# Top_Level.net
KiCad netlist of a schematic drawn in Altium Designer
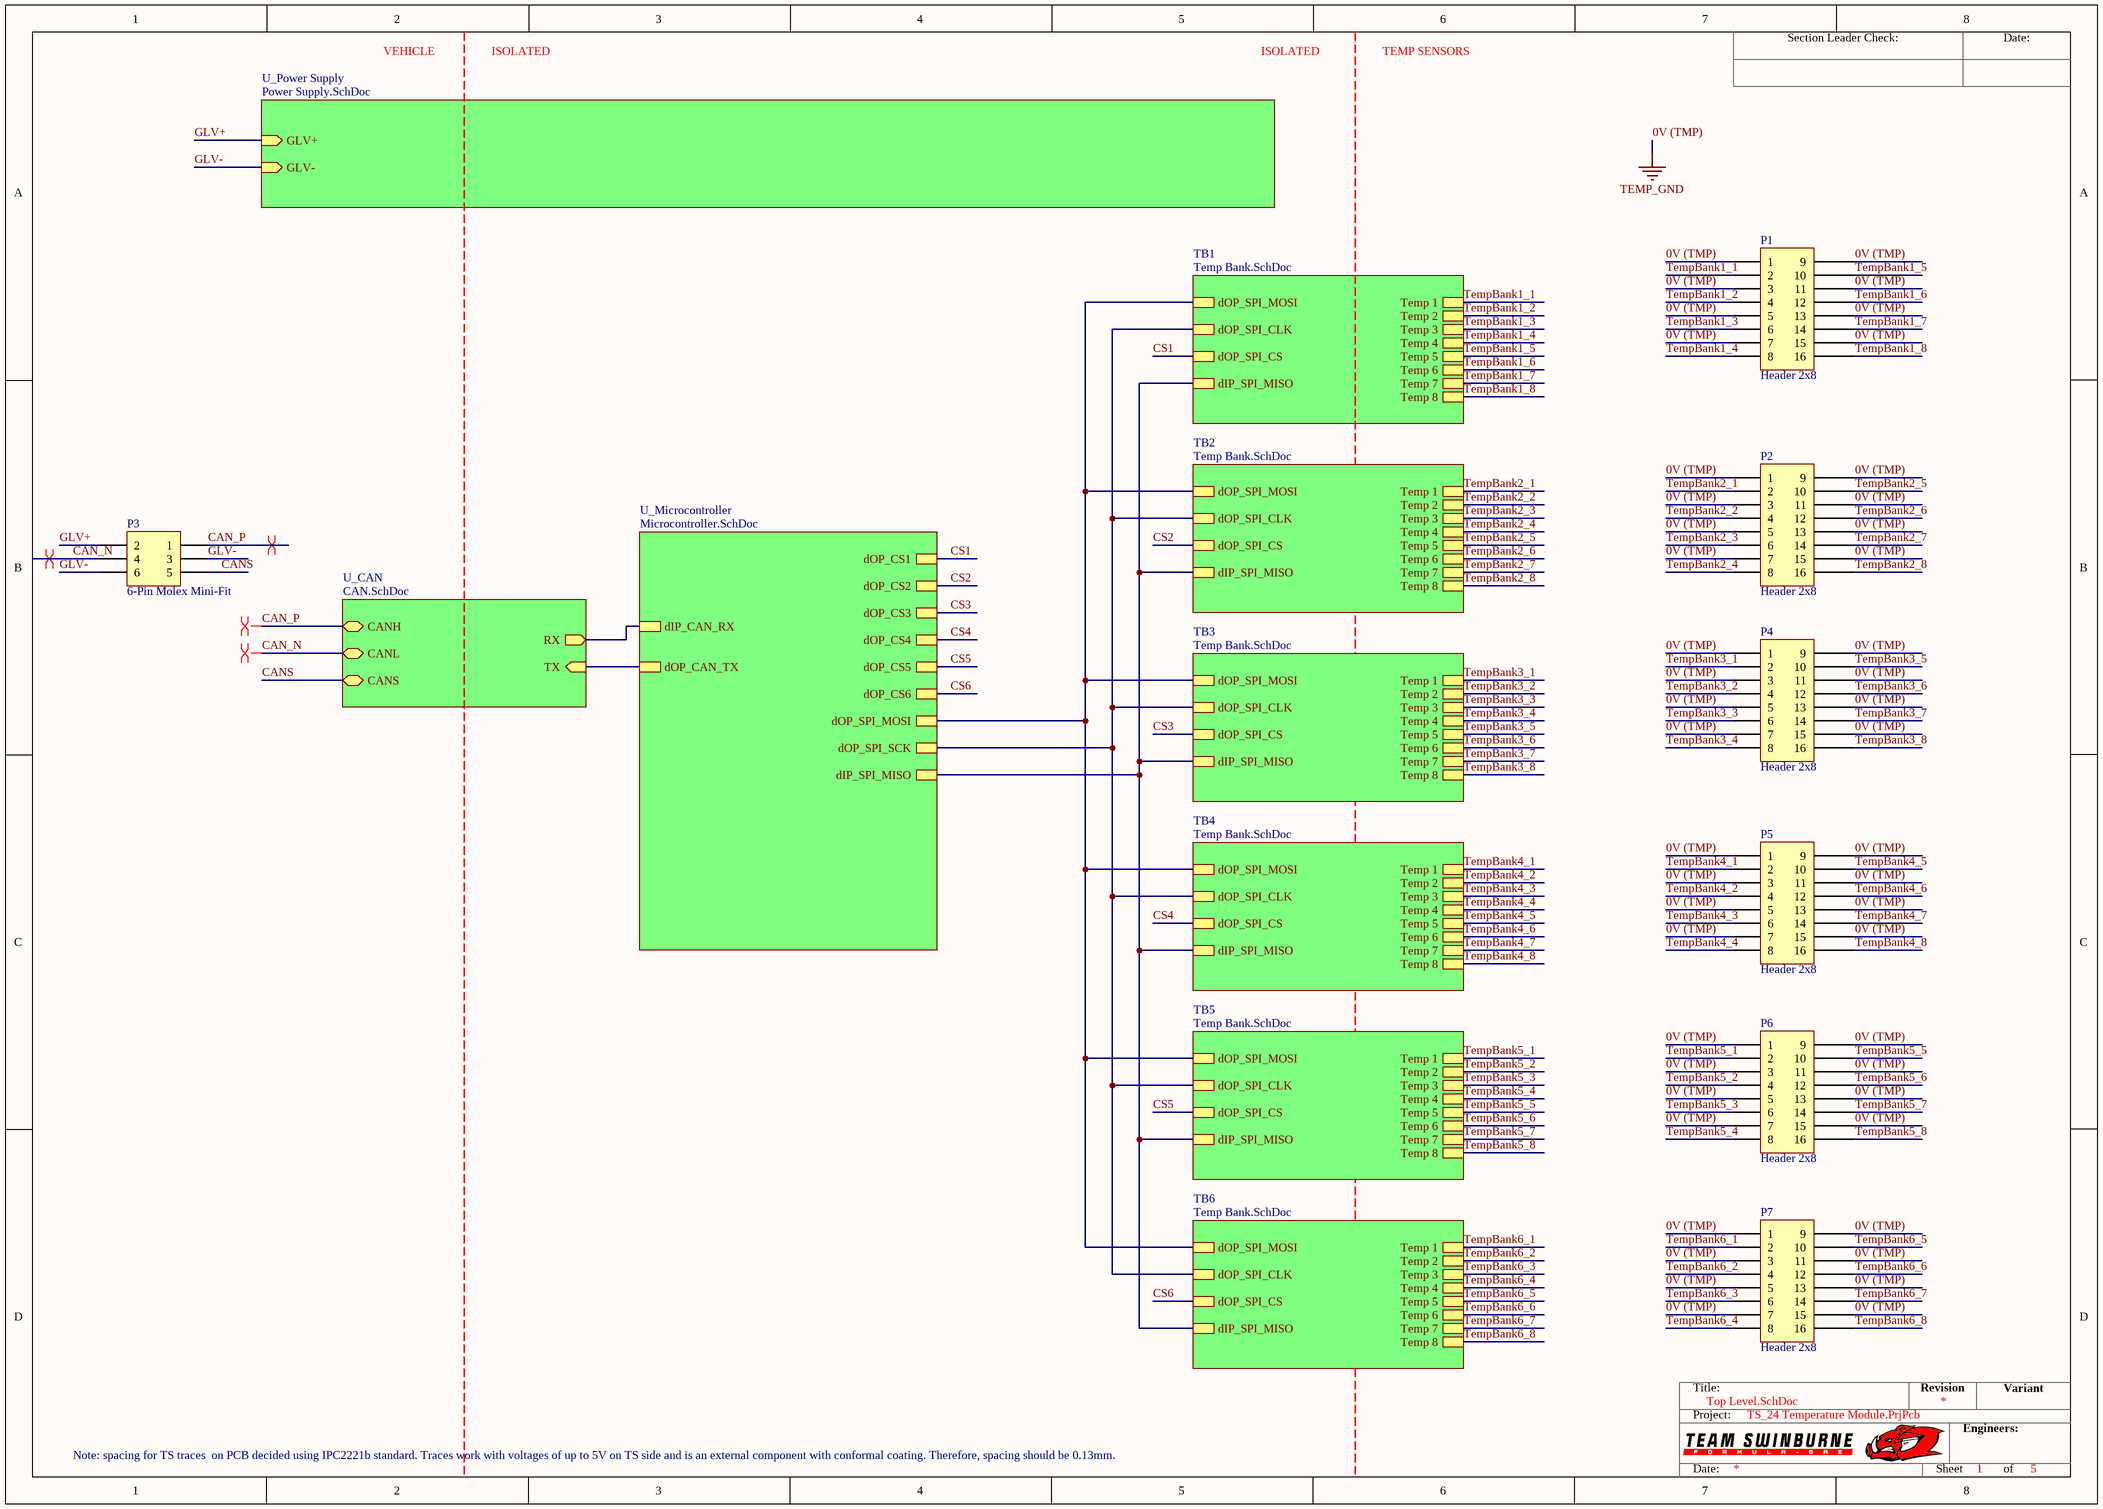
[diagram p0: Top Level.SchDoc]

(export (version "E")
  (design (tool "Eeschema 10.0.6"))
  (components
    (comp (ref "P1")
      (value "Header 2x8")
      (footprint "B16B-PHDSS")
      (fields (field (name "PART NUMBER") "B16B-PHDSS") (field (name "CONTACT") "Tin"))
      (libsource (lib "ts_standard_connectors") (part "Header 2x8"))
    )
    (comp (ref "P2")
      (value "Header 2x8")
      (footprint "B16B-PHDSS")
      (fields (field (name "PART NUMBER") "B16B-PHDSS") (field (name "CONTACT") "Tin"))
      (libsource (lib "ts_standard_connectors") (part "Header 2x8"))
    )
    (comp (ref "P3")
      (value "6-Pin Molex Mini-Fit")
      (footprint "6-Pin Molex Mini-Fit")
      (description "6-Pin Molex Mini-Fit Connector Header 6 pin mini fit")
      (libsource (lib "Team Swinburne") (part "3x2-Pin connector"))
    )
    (comp (ref "P4")
      (value "Header 2x8")
      (footprint "B16B-PHDSS")
      (fields (field (name "PART NUMBER") "B16B-PHDSS") (field (name "CONTACT") "Tin"))
      (libsource (lib "ts_standard_connectors") (part "Header 2x8"))
    )
    (comp (ref "P5")
      (value "Header 2x8")
      (footprint "B16B-PHDSS")
      (fields (field (name "PART NUMBER") "B16B-PHDSS") (field (name "CONTACT") "Tin"))
      (libsource (lib "ts_standard_connectors") (part "Header 2x8"))
    )
    (comp (ref "P6")
      (value "Header 2x8")
      (footprint "B16B-PHDSS")
      (fields (field (name "PART NUMBER") "B16B-PHDSS") (field (name "CONTACT") "Tin"))
      (libsource (lib "ts_standard_connectors") (part "Header 2x8"))
    )
    (comp (ref "P7")
      (value "Header 2x8")
      (footprint "B16B-PHDSS")
      (fields (field (name "PART NUMBER") "B16B-PHDSS") (field (name "CONTACT") "Tin"))
      (libsource (lib "ts_standard_connectors") (part "Header 2x8"))
    )
  )
  (nets
    (net (code "2") (name "/CANS") (class "Default")
      (node (ref "P3") (pin "5") (pinfunction "5_5") (pintype "passive"))
    )
    (net (code "3") (name "/CAN_N") (class "Default")
      (node (ref "P3") (pin "4") (pinfunction "4_4") (pintype "passive"))
    )
    (net (code "4") (name "/CAN_P") (class "Default")
      (node (ref "P3") (pin "1") (pinfunction "1_1") (pintype "passive"))
    )
    (net (code "11") (name "/GLV+") (class "Default")
      (node (ref "P3") (pin "2") (pinfunction "2_2") (pintype "passive"))
    )
    (net (code "12") (name "/GLV-") (class "Default")
      (node (ref "P3") (pin "3") (pinfunction "3_3") (pintype "passive"))
      (node (ref "P3") (pin "6") (pinfunction "6_6") (pintype "passive"))
    )
    (net (code "15") (name "/TempBank1_1") (class "Default")
      (node (ref "P1") (pin "2") (pinfunction "2_2") (pintype "passive"))
    )
    (net (code "16") (name "/TempBank1_2") (class "Default")
      (node (ref "P1") (pin "4") (pinfunction "4_4") (pintype "passive"))
    )
    (net (code "17") (name "/TempBank1_3") (class "Default")
      (node (ref "P1") (pin "6") (pinfunction "6_6") (pintype "passive"))
    )
    (net (code "18") (name "/TempBank1_4") (class "Default")
      (node (ref "P1") (pin "8") (pinfunction "8_8") (pintype "passive"))
    )
    (net (code "19") (name "/TempBank1_5") (class "Default")
      (node (ref "P1") (pin "10") (pinfunction "10_10") (pintype "passive"))
    )
    (net (code "20") (name "/TempBank1_6") (class "Default")
      (node (ref "P1") (pin "12") (pinfunction "12_12") (pintype "passive"))
    )
    (net (code "21") (name "/TempBank1_7") (class "Default")
      (node (ref "P1") (pin "14") (pinfunction "14_14") (pintype "passive"))
    )
    (net (code "22") (name "/TempBank1_8") (class "Default")
      (node (ref "P1") (pin "16") (pinfunction "16_16") (pintype "passive"))
    )
    (net (code "23") (name "/TempBank2_1") (class "Default")
      (node (ref "P2") (pin "2") (pinfunction "2_2") (pintype "passive"))
    )
    (net (code "24") (name "/TempBank2_2") (class "Default")
      (node (ref "P2") (pin "4") (pinfunction "4_4") (pintype "passive"))
    )
    (net (code "25") (name "/TempBank2_3") (class "Default")
      (node (ref "P2") (pin "6") (pinfunction "6_6") (pintype "passive"))
    )
    (net (code "26") (name "/TempBank2_4") (class "Default")
      (node (ref "P2") (pin "8") (pinfunction "8_8") (pintype "passive"))
    )
    (net (code "27") (name "/TempBank2_5") (class "Default")
      (node (ref "P2") (pin "10") (pinfunction "10_10") (pintype "passive"))
    )
    (net (code "28") (name "/TempBank2_6") (class "Default")
      (node (ref "P2") (pin "12") (pinfunction "12_12") (pintype "passive"))
    )
    (net (code "29") (name "/TempBank2_7") (class "Default")
      (node (ref "P2") (pin "14") (pinfunction "14_14") (pintype "passive"))
    )
    (net (code "30") (name "/TempBank2_8") (class "Default")
      (node (ref "P2") (pin "16") (pinfunction "16_16") (pintype "passive"))
    )
    (net (code "31") (name "/TempBank3_1") (class "Default")
      (node (ref "P4") (pin "2") (pinfunction "2_2") (pintype "passive"))
    )
    (net (code "32") (name "/TempBank3_2") (class "Default")
      (node (ref "P4") (pin "4") (pinfunction "4_4") (pintype "passive"))
    )
    (net (code "33") (name "/TempBank3_3") (class "Default")
      (node (ref "P4") (pin "6") (pinfunction "6_6") (pintype "passive"))
    )
    (net (code "34") (name "/TempBank3_4") (class "Default")
      (node (ref "P4") (pin "8") (pinfunction "8_8") (pintype "passive"))
    )
    (net (code "35") (name "/TempBank3_5") (class "Default")
      (node (ref "P4") (pin "10") (pinfunction "10_10") (pintype "passive"))
    )
    (net (code "36") (name "/TempBank3_6") (class "Default")
      (node (ref "P4") (pin "12") (pinfunction "12_12") (pintype "passive"))
    )
    (net (code "37") (name "/TempBank3_7") (class "Default")
      (node (ref "P4") (pin "14") (pinfunction "14_14") (pintype "passive"))
    )
    (net (code "38") (name "/TempBank3_8") (class "Default")
      (node (ref "P4") (pin "16") (pinfunction "16_16") (pintype "passive"))
    )
    (net (code "39") (name "/TempBank4_1") (class "Default")
      (node (ref "P5") (pin "2") (pinfunction "2_2") (pintype "passive"))
    )
    (net (code "40") (name "/TempBank4_2") (class "Default")
      (node (ref "P5") (pin "4") (pinfunction "4_4") (pintype "passive"))
    )
    (net (code "41") (name "/TempBank4_3") (class "Default")
      (node (ref "P5") (pin "6") (pinfunction "6_6") (pintype "passive"))
    )
    (net (code "42") (name "/TempBank4_4") (class "Default")
      (node (ref "P5") (pin "8") (pinfunction "8_8") (pintype "passive"))
    )
    (net (code "43") (name "/TempBank4_5") (class "Default")
      (node (ref "P5") (pin "10") (pinfunction "10_10") (pintype "passive"))
    )
    (net (code "44") (name "/TempBank4_6") (class "Default")
      (node (ref "P5") (pin "12") (pinfunction "12_12") (pintype "passive"))
    )
    (net (code "45") (name "/TempBank4_7") (class "Default")
      (node (ref "P5") (pin "14") (pinfunction "14_14") (pintype "passive"))
    )
    (net (code "46") (name "/TempBank4_8") (class "Default")
      (node (ref "P5") (pin "16") (pinfunction "16_16") (pintype "passive"))
    )
    (net (code "47") (name "/TempBank5_1") (class "Default")
      (node (ref "P6") (pin "2") (pinfunction "2_2") (pintype "passive"))
    )
    (net (code "48") (name "/TempBank5_2") (class "Default")
      (node (ref "P6") (pin "4") (pinfunction "4_4") (pintype "passive"))
    )
    (net (code "49") (name "/TempBank5_3") (class "Default")
      (node (ref "P6") (pin "6") (pinfunction "6_6") (pintype "passive"))
    )
    (net (code "50") (name "/TempBank5_4") (class "Default")
      (node (ref "P6") (pin "8") (pinfunction "8_8") (pintype "passive"))
    )
    (net (code "51") (name "/TempBank5_5") (class "Default")
      (node (ref "P6") (pin "10") (pinfunction "10_10") (pintype "passive"))
    )
    (net (code "52") (name "/TempBank5_6") (class "Default")
      (node (ref "P6") (pin "12") (pinfunction "12_12") (pintype "passive"))
    )
    (net (code "53") (name "/TempBank5_7") (class "Default")
      (node (ref "P6") (pin "14") (pinfunction "14_14") (pintype "passive"))
    )
    (net (code "54") (name "/TempBank5_8") (class "Default")
      (node (ref "P6") (pin "16") (pinfunction "16_16") (pintype "passive"))
    )
    (net (code "55") (name "/TempBank6_1") (class "Default")
      (node (ref "P7") (pin "2") (pinfunction "2_2") (pintype "passive"))
    )
    (net (code "56") (name "/TempBank6_2") (class "Default")
      (node (ref "P7") (pin "4") (pinfunction "4_4") (pintype "passive"))
    )
    (net (code "57") (name "/TempBank6_3") (class "Default")
      (node (ref "P7") (pin "6") (pinfunction "6_6") (pintype "passive"))
    )
    (net (code "58") (name "/TempBank6_4") (class "Default")
      (node (ref "P7") (pin "8") (pinfunction "8_8") (pintype "passive"))
    )
    (net (code "59") (name "/TempBank6_5") (class "Default")
      (node (ref "P7") (pin "10") (pinfunction "10_10") (pintype "passive"))
    )
    (net (code "60") (name "/TempBank6_6") (class "Default")
      (node (ref "P7") (pin "12") (pinfunction "12_12") (pintype "passive"))
    )
    (net (code "61") (name "/TempBank6_7") (class "Default")
      (node (ref "P7") (pin "14") (pinfunction "14_14") (pintype "passive"))
    )
    (net (code "62") (name "/TempBank6_8") (class "Default")
      (node (ref "P7") (pin "16") (pinfunction "16_16") (pintype "passive"))
    )
    (net (code "66") (name "TEMP_GND") (class "Default")
      (node (ref "P1") (pin "1") (pinfunction "1_1") (pintype "passive"))
      (node (ref "P1") (pin "11") (pinfunction "11_11") (pintype "passive"))
      (node (ref "P1") (pin "13") (pinfunction "13_13") (pintype "passive"))
      (node (ref "P1") (pin "15") (pinfunction "15_15") (pintype "passive"))
      (node (ref "P1") (pin "3") (pinfunction "3_3") (pintype "passive"))
      (node (ref "P1") (pin "5") (pinfunction "5_5") (pintype "passive"))
      (node (ref "P1") (pin "7") (pinfunction "7_7") (pintype "passive"))
      (node (ref "P1") (pin "9") (pinfunction "9_9") (pintype "passive"))
      (node (ref "P2") (pin "1") (pinfunction "1_1") (pintype "passive"))
      (node (ref "P2") (pin "11") (pinfunction "11_11") (pintype "passive"))
      (node (ref "P2") (pin "13") (pinfunction "13_13") (pintype "passive"))
      (node (ref "P2") (pin "15") (pinfunction "15_15") (pintype "passive"))
      (node (ref "P2") (pin "3") (pinfunction "3_3") (pintype "passive"))
      (node (ref "P2") (pin "5") (pinfunction "5_5") (pintype "passive"))
      (node (ref "P2") (pin "7") (pinfunction "7_7") (pintype "passive"))
      (node (ref "P2") (pin "9") (pinfunction "9_9") (pintype "passive"))
      (node (ref "P4") (pin "1") (pinfunction "1_1") (pintype "passive"))
      (node (ref "P4") (pin "11") (pinfunction "11_11") (pintype "passive"))
      (node (ref "P4") (pin "13") (pinfunction "13_13") (pintype "passive"))
      (node (ref "P4") (pin "15") (pinfunction "15_15") (pintype "passive"))
      (node (ref "P4") (pin "3") (pinfunction "3_3") (pintype "passive"))
      (node (ref "P4") (pin "5") (pinfunction "5_5") (pintype "passive"))
      (node (ref "P4") (pin "7") (pinfunction "7_7") (pintype "passive"))
      (node (ref "P4") (pin "9") (pinfunction "9_9") (pintype "passive"))
      (node (ref "P5") (pin "1") (pinfunction "1_1") (pintype "passive"))
      (node (ref "P5") (pin "11") (pinfunction "11_11") (pintype "passive"))
      (node (ref "P5") (pin "13") (pinfunction "13_13") (pintype "passive"))
      (node (ref "P5") (pin "15") (pinfunction "15_15") (pintype "passive"))
      (node (ref "P5") (pin "3") (pinfunction "3_3") (pintype "passive"))
      (node (ref "P5") (pin "5") (pinfunction "5_5") (pintype "passive"))
      (node (ref "P5") (pin "7") (pinfunction "7_7") (pintype "passive"))
      (node (ref "P5") (pin "9") (pinfunction "9_9") (pintype "passive"))
      (node (ref "P6") (pin "1") (pinfunction "1_1") (pintype "passive"))
      (node (ref "P6") (pin "11") (pinfunction "11_11") (pintype "passive"))
      (node (ref "P6") (pin "13") (pinfunction "13_13") (pintype "passive"))
      (node (ref "P6") (pin "15") (pinfunction "15_15") (pintype "passive"))
      (node (ref "P6") (pin "3") (pinfunction "3_3") (pintype "passive"))
      (node (ref "P6") (pin "5") (pinfunction "5_5") (pintype "passive"))
      (node (ref "P6") (pin "7") (pinfunction "7_7") (pintype "passive"))
      (node (ref "P6") (pin "9") (pinfunction "9_9") (pintype "passive"))
      (node (ref "P7") (pin "1") (pinfunction "1_1") (pintype "passive"))
      (node (ref "P7") (pin "11") (pinfunction "11_11") (pintype "passive"))
      (node (ref "P7") (pin "13") (pinfunction "13_13") (pintype "passive"))
      (node (ref "P7") (pin "15") (pinfunction "15_15") (pintype "passive"))
      (node (ref "P7") (pin "3") (pinfunction "3_3") (pintype "passive"))
      (node (ref "P7") (pin "5") (pinfunction "5_5") (pintype "passive"))
      (node (ref "P7") (pin "7") (pinfunction "7_7") (pintype "passive"))
      (node (ref "P7") (pin "9") (pinfunction "9_9") (pintype "passive"))
    )
  )
)
